# xilinx_platform_cable_iii.net
KiCad netlist of a schematic drawn in EAGLE
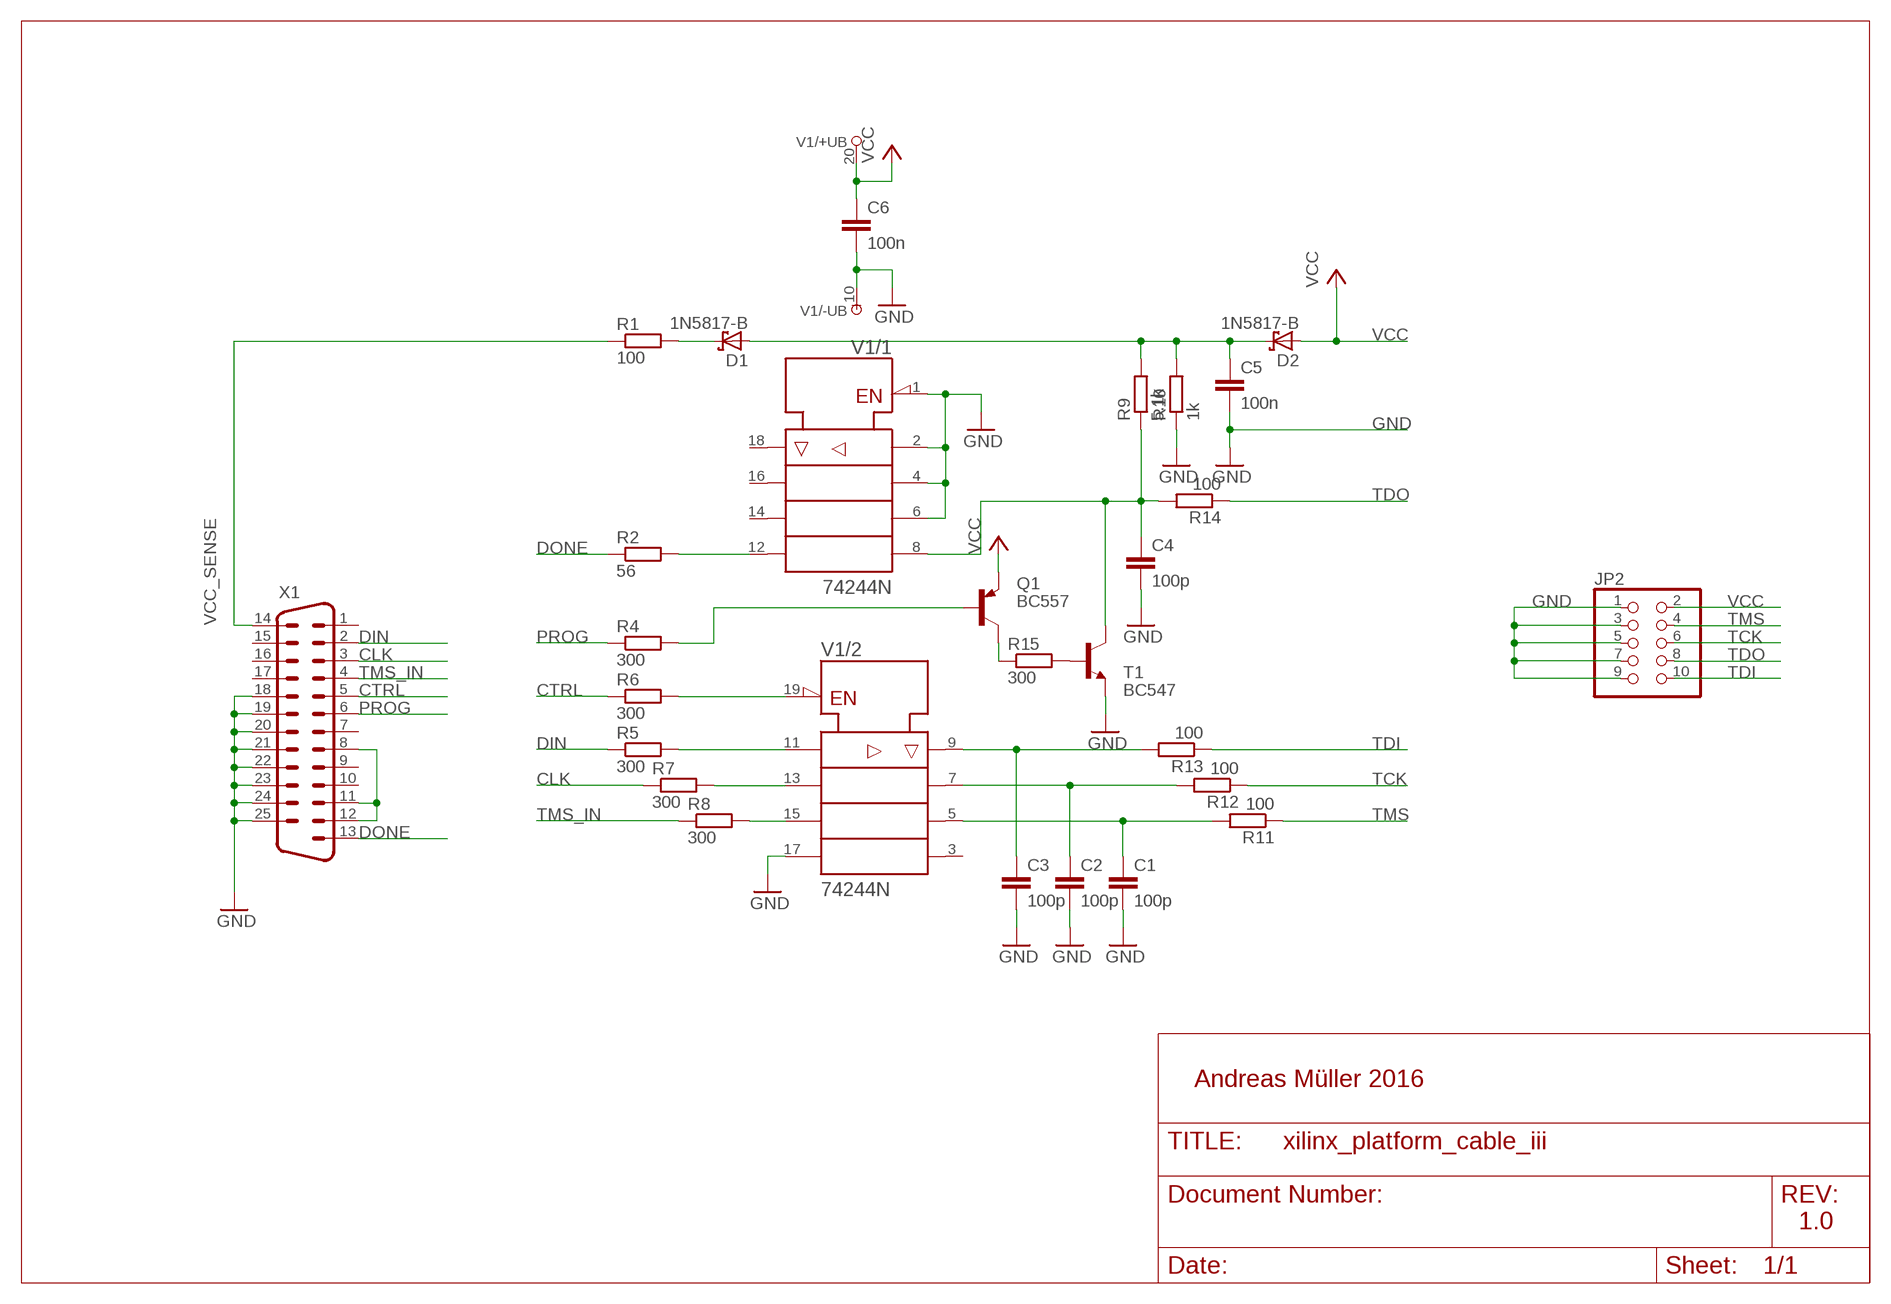
[diagram p0: schematic, sheet 1]

(export (version "E")
  (design (tool "Eeschema 10.0.6"))
  (components
    (comp (ref "C1")
      (value "100p")
      (footprint "eagle-import:C025-030X050")
      (libsource (lib "eagle-import") (part "C-EU025-030X050"))
    )
    (comp (ref "C2")
      (value "100p")
      (footprint "eagle-import:C025-030X050")
      (libsource (lib "eagle-import") (part "C-EU025-030X050"))
    )
    (comp (ref "C3")
      (value "100p")
      (footprint "eagle-import:C025-030X050")
      (libsource (lib "eagle-import") (part "C-EU025-030X050"))
    )
    (comp (ref "C4")
      (value "100p")
      (footprint "eagle-import:C025-030X050")
      (libsource (lib "eagle-import") (part "C-EU025-030X050"))
    )
    (comp (ref "C5")
      (value "100n")
      (footprint "eagle-import:C025-030X050")
      (libsource (lib "eagle-import") (part "C-EU025-030X050"))
    )
    (comp (ref "C6")
      (value "100n")
      (footprint "eagle-import:C025-030X050")
      (libsource (lib "eagle-import") (part "C-EU025-030X050"))
    )
    (comp (ref "D1")
      (value "1N5817-B")
      (footprint "eagle-import:DO41-7.6")
      (libsource (lib "eagle-import") (part "1N5817-B"))
    )
    (comp (ref "D2")
      (value "1N5817-B")
      (footprint "eagle-import:DO41-7.6")
      (libsource (lib "eagle-import") (part "1N5817-B"))
    )
    (comp (ref "JP2")
      (value "PINHD-2X5")
      (footprint "eagle-import:2X05")
      (libsource (lib "eagle-import") (part "PINHD-2X5"))
    )
    (comp (ref "Q1")
      (value "BC557")
      (footprint "eagle-import:TO92")
      (libsource (lib "eagle-import") (part "BC557"))
    )
    (comp (ref "R1")
      (value "100")
      (footprint "eagle-import:0207_12")
      (libsource (lib "eagle-import") (part "R-EU_0207/12"))
    )
    (comp (ref "R2")
      (value "56")
      (footprint "eagle-import:0207_12")
      (libsource (lib "eagle-import") (part "R-EU_0207/12"))
    )
    (comp (ref "R4")
      (value "300")
      (footprint "eagle-import:0207_12")
      (libsource (lib "eagle-import") (part "R-EU_0207/12"))
    )
    (comp (ref "R5")
      (value "300")
      (footprint "eagle-import:0207_12")
      (libsource (lib "eagle-import") (part "R-EU_0207/12"))
    )
    (comp (ref "R6")
      (value "300")
      (footprint "eagle-import:0207_12")
      (libsource (lib "eagle-import") (part "R-EU_0207/12"))
    )
    (comp (ref "R7")
      (value "300")
      (footprint "eagle-import:0207_12")
      (libsource (lib "eagle-import") (part "R-EU_0207/12"))
    )
    (comp (ref "R8")
      (value "300")
      (footprint "eagle-import:0207_12")
      (libsource (lib "eagle-import") (part "R-EU_0207/12"))
    )
    (comp (ref "R9")
      (value "5.1k")
      (footprint "eagle-import:0207_12")
      (libsource (lib "eagle-import") (part "R-EU_0207/12"))
    )
    (comp (ref "R10")
      (value "1k")
      (footprint "eagle-import:0207_12")
      (libsource (lib "eagle-import") (part "R-EU_0207/12"))
    )
    (comp (ref "R11")
      (value "100")
      (footprint "eagle-import:0207_12")
      (libsource (lib "eagle-import") (part "R-EU_0207/12"))
    )
    (comp (ref "R12")
      (value "100")
      (footprint "eagle-import:0207_12")
      (libsource (lib "eagle-import") (part "R-EU_0207/12"))
    )
    (comp (ref "R13")
      (value "100")
      (footprint "eagle-import:0207_12")
      (libsource (lib "eagle-import") (part "R-EU_0207/12"))
    )
    (comp (ref "R14")
      (value "100")
      (footprint "eagle-import:0207_12")
      (libsource (lib "eagle-import") (part "R-EU_0207/12"))
    )
    (comp (ref "R15")
      (value "300")
      (footprint "eagle-import:0207_12")
      (libsource (lib "eagle-import") (part "R-EU_0207/12"))
    )
    (comp (ref "T1")
      (value "BC547")
      (footprint "eagle-import:TO92")
      (libsource (lib "eagle-import") (part "BC547"))
    )
    (comp (ref "V1")
      (value "74244N")
      (footprint "eagle-import:DIL20")
      (libsource (lib "eagle-import") (part "74244N"))
    )
    (comp (ref "X1")
      (value "DB25HP")
      (footprint "eagle-import:M25HP")
      (libsource (lib "eagle-import") (part "DB25HP"))
    )
  )
  (nets
    (net (code "1") (name "/CLK") (class "Default")
      (node (ref "R7") (pin "1") (pinfunction "1_1") (pintype "passive"))
      (node (ref "X1") (pin "3") (pinfunction "3_3") (pintype "passive"))
    )
    (net (code "2") (name "/CTRL") (class "Default")
      (node (ref "R6") (pin "1") (pinfunction "1_1") (pintype "passive"))
      (node (ref "X1") (pin "5") (pinfunction "5_5") (pintype "passive"))
    )
    (net (code "3") (name "/DIN") (class "Default")
      (node (ref "R5") (pin "1") (pinfunction "1_1") (pintype "passive"))
      (node (ref "X1") (pin "2") (pinfunction "2_2") (pintype "passive"))
    )
    (net (code "4") (name "/DONE") (class "Default")
      (node (ref "R2") (pin "1") (pinfunction "1_1") (pintype "passive"))
      (node (ref "X1") (pin "13") (pinfunction "13_13") (pintype "passive"))
    )
    (net (code "5") (name "/PROG") (class "Default")
      (node (ref "R4") (pin "1") (pinfunction "1_1") (pintype "passive"))
      (node (ref "X1") (pin "6") (pinfunction "6_6") (pintype "passive"))
    )
    (net (code "6") (name "/TCK") (class "Default")
      (node (ref "JP2") (pin "6") (pinfunction "6_6") (pintype "passive"))
      (node (ref "R12") (pin "1") (pinfunction "1_1") (pintype "passive"))
    )
    (net (code "7") (name "/TDI") (class "Default")
      (node (ref "JP2") (pin "10") (pinfunction "10_10") (pintype "passive"))
      (node (ref "R13") (pin "1") (pinfunction "1_1") (pintype "passive"))
    )
    (net (code "8") (name "/TDO") (class "Default")
      (node (ref "JP2") (pin "8") (pinfunction "8_8") (pintype "passive"))
      (node (ref "R14") (pin "1") (pinfunction "1_1") (pintype "passive"))
    )
    (net (code "9") (name "/TMS") (class "Default")
      (node (ref "JP2") (pin "4") (pinfunction "4_4") (pintype "passive"))
      (node (ref "R11") (pin "1") (pinfunction "1_1") (pintype "passive"))
    )
    (net (code "10") (name "/TMS_IN") (class "Default")
      (node (ref "R8") (pin "1") (pinfunction "1_1") (pintype "passive"))
      (node (ref "X1") (pin "4") (pinfunction "4_4") (pintype "passive"))
    )
    (net (code "11") (name "/VCC_SENSE") (class "Default")
      (node (ref "R1") (pin "1") (pinfunction "1_1") (pintype "passive"))
      (node (ref "X1") (pin "14") (pinfunction "14_14") (pintype "passive"))
    )
    (net (code "12") (name "GND") (class "Default")
      (node (ref "C1") (pin "2") (pinfunction "2_2") (pintype "passive"))
      (node (ref "C2") (pin "2") (pinfunction "2_2") (pintype "passive"))
      (node (ref "C3") (pin "2") (pinfunction "2_2") (pintype "passive"))
      (node (ref "C4") (pin "2") (pinfunction "2_2") (pintype "passive"))
      (node (ref "C5") (pin "2") (pinfunction "2_2") (pintype "passive"))
      (node (ref "C6") (pin "2") (pinfunction "2_2") (pintype "passive"))
      (node (ref "JP2") (pin "1") (pinfunction "1_1") (pintype "passive"))
      (node (ref "JP2") (pin "3") (pinfunction "3_3") (pintype "passive"))
      (node (ref "JP2") (pin "5") (pinfunction "5_5") (pintype "passive"))
      (node (ref "JP2") (pin "7") (pinfunction "7_7") (pintype "passive"))
      (node (ref "JP2") (pin "9") (pinfunction "9_9") (pintype "passive"))
      (node (ref "R10") (pin "1") (pinfunction "1_1") (pintype "passive"))
      (node (ref "T1") (pin "1") (pinfunction "E_1") (pintype "passive"))
      (node (ref "V1") (pin "1") (pinfunction "~{G}_1") (pintype "input"))
      (node (ref "V1") (pin "10") (pinfunction "-UB_10") (pintype "power_in"))
      (node (ref "V1") (pin "17") (pinfunction "A4_17") (pintype "input"))
      (node (ref "V1") (pin "2") (pinfunction "A1_2") (pintype "input"))
      (node (ref "V1") (pin "4") (pinfunction "A2_4") (pintype "input"))
      (node (ref "V1") (pin "6") (pinfunction "A3_6") (pintype "input"))
      (node (ref "X1") (pin "18") (pinfunction "18_18") (pintype "passive"))
      (node (ref "X1") (pin "19") (pinfunction "19_19") (pintype "passive"))
      (node (ref "X1") (pin "20") (pinfunction "20_20") (pintype "passive"))
      (node (ref "X1") (pin "21") (pinfunction "21_21") (pintype "passive"))
      (node (ref "X1") (pin "22") (pinfunction "22_22") (pintype "passive"))
      (node (ref "X1") (pin "23") (pinfunction "23_23") (pintype "passive"))
      (node (ref "X1") (pin "24") (pinfunction "24_24") (pintype "passive"))
      (node (ref "X1") (pin "25") (pinfunction "25_25") (pintype "passive"))
    )
    (net (code "13") (name "Net-(C5-Pad1)") (class "Default")
      (node (ref "C5") (pin "1") (pinfunction "1_1") (pintype "passive"))
      (node (ref "D1") (pin "A") (pinfunction "A_A") (pintype "passive"))
      (node (ref "D2") (pin "C") (pinfunction "C_C") (pintype "passive"))
      (node (ref "R10") (pin "2") (pinfunction "2_2") (pintype "passive"))
      (node (ref "R9") (pin "2") (pinfunction "2_2") (pintype "passive"))
    )
    (net (code "14") (name "Net-(D1-PadC)") (class "Default")
      (node (ref "D1") (pin "C") (pinfunction "C_C") (pintype "passive"))
      (node (ref "R1") (pin "2") (pinfunction "2_2") (pintype "passive"))
    )
    (net (code "15") (name "Net-(Q1-B)") (class "Default")
      (node (ref "Q1") (pin "2") (pinfunction "B_2") (pintype "passive"))
      (node (ref "R4") (pin "2") (pinfunction "2_2") (pintype "passive"))
    )
    (net (code "16") (name "Net-(Q1-C)") (class "Default")
      (node (ref "Q1") (pin "3") (pinfunction "C_3") (pintype "passive"))
      (node (ref "R15") (pin "1") (pinfunction "1_1") (pintype "passive"))
    )
    (net (code "17") (name "Net-(T1-B)") (class "Default")
      (node (ref "R15") (pin "2") (pinfunction "2_2") (pintype "passive"))
      (node (ref "T1") (pin "2") (pinfunction "B_2") (pintype "passive"))
    )
    (net (code "18") (name "Net-(T1-C)") (class "Default")
      (node (ref "C4") (pin "1") (pinfunction "1_1") (pintype "passive"))
      (node (ref "R14") (pin "2") (pinfunction "2_2") (pintype "passive"))
      (node (ref "R9") (pin "1") (pinfunction "1_1") (pintype "passive"))
      (node (ref "T1") (pin "3") (pinfunction "C_3") (pintype "passive"))
      (node (ref "V1") (pin "8") (pinfunction "A4_8") (pintype "input"))
    )
    (net (code "19") (name "Net-(V1C-Y4)") (class "Default")
      (node (ref "R2") (pin "2") (pinfunction "2_2") (pintype "passive"))
      (node (ref "V1") (pin "12") (pinfunction "Y4_12") (pintype "tri_state"))
    )
    (net (code "20") (name "Net-(V1D-A1)") (class "Default")
      (node (ref "R5") (pin "2") (pinfunction "2_2") (pintype "passive"))
      (node (ref "V1") (pin "11") (pinfunction "A1_11") (pintype "input"))
    )
    (net (code "21") (name "Net-(V1D-A2)") (class "Default")
      (node (ref "R7") (pin "2") (pinfunction "2_2") (pintype "passive"))
      (node (ref "V1") (pin "13") (pinfunction "A2_13") (pintype "input"))
    )
    (net (code "22") (name "Net-(V1D-A3)") (class "Default")
      (node (ref "R8") (pin "2") (pinfunction "2_2") (pintype "passive"))
      (node (ref "V1") (pin "15") (pinfunction "A3_15") (pintype "input"))
    )
    (net (code "23") (name "Net-(V1D-Y1)") (class "Default")
      (node (ref "C3") (pin "1") (pinfunction "1_1") (pintype "passive"))
      (node (ref "R13") (pin "2") (pinfunction "2_2") (pintype "passive"))
      (node (ref "V1") (pin "9") (pinfunction "Y1_9") (pintype "tri_state"))
    )
    (net (code "24") (name "Net-(V1D-Y2)") (class "Default")
      (node (ref "C2") (pin "1") (pinfunction "1_1") (pintype "passive"))
      (node (ref "R12") (pin "2") (pinfunction "2_2") (pintype "passive"))
      (node (ref "V1") (pin "7") (pinfunction "Y2_7") (pintype "tri_state"))
    )
    (net (code "25") (name "Net-(V1D-Y3)") (class "Default")
      (node (ref "C1") (pin "1") (pinfunction "1_1") (pintype "passive"))
      (node (ref "R11") (pin "2") (pinfunction "2_2") (pintype "passive"))
      (node (ref "V1") (pin "5") (pinfunction "Y3_5") (pintype "tri_state"))
    )
    (net (code "26") (name "Net-(V1D-~{G})") (class "Default")
      (node (ref "R6") (pin "2") (pinfunction "2_2") (pintype "passive"))
      (node (ref "V1") (pin "19") (pinfunction "~{G}_19") (pintype "input"))
    )
    (net (code "27") (name "Net-(X1-Pad11)") (class "Default")
      (node (ref "X1") (pin "11") (pinfunction "11_11") (pintype "passive"))
      (node (ref "X1") (pin "12") (pinfunction "12_12") (pintype "passive"))
      (node (ref "X1") (pin "8") (pinfunction "8_8") (pintype "passive"))
    )
    (net (code "28") (name "VCC") (class "Default")
      (node (ref "C6") (pin "1") (pinfunction "1_1") (pintype "passive"))
      (node (ref "D2") (pin "A") (pinfunction "A_A") (pintype "passive"))
      (node (ref "JP2") (pin "2") (pinfunction "2_2") (pintype "passive"))
      (node (ref "Q1") (pin "1") (pinfunction "E_1") (pintype "passive"))
      (node (ref "V1") (pin "20") (pinfunction "+UB_20") (pintype "power_in"))
    )
    (net (code "29") (name "unconnected-(V1C-Y1-Pad18)") (class "Default")
      (node (ref "V1") (pin "18") (pinfunction "Y1_18") (pintype "tri_state"))
    )
    (net (code "30") (name "unconnected-(V1C-Y2-Pad16)") (class "Default")
      (node (ref "V1") (pin "16") (pinfunction "Y2_16") (pintype "tri_state"))
    )
    (net (code "31") (name "unconnected-(V1C-Y3-Pad14)") (class "Default")
      (node (ref "V1") (pin "14") (pinfunction "Y3_14") (pintype "tri_state"))
    )
    (net (code "32") (name "unconnected-(V1D-Y4-Pad3)") (class "Default")
      (node (ref "V1") (pin "3") (pinfunction "Y4_3") (pintype "tri_state"))
    )
    (net (code "33") (name "unconnected-(X1-Pad1)") (class "Default")
      (node (ref "X1") (pin "1") (pinfunction "1_1") (pintype "passive"))
    )
    (net (code "34") (name "unconnected-(X1-Pad7)") (class "Default")
      (node (ref "X1") (pin "7") (pinfunction "7_7") (pintype "passive"))
    )
    (net (code "35") (name "unconnected-(X1-Pad9)") (class "Default")
      (node (ref "X1") (pin "9") (pinfunction "9_9") (pintype "passive"))
    )
    (net (code "36") (name "unconnected-(X1-Pad10)") (class "Default")
      (node (ref "X1") (pin "10") (pinfunction "10_10") (pintype "passive"))
    )
    (net (code "37") (name "unconnected-(X1-Pad15)") (class "Default")
      (node (ref "X1") (pin "15") (pinfunction "15_15") (pintype "passive"))
    )
    (net (code "38") (name "unconnected-(X1-Pad16)") (class "Default")
      (node (ref "X1") (pin "16") (pinfunction "16_16") (pintype "passive"))
    )
    (net (code "39") (name "unconnected-(X1-Pad17)") (class "Default")
      (node (ref "X1") (pin "17") (pinfunction "17_17") (pintype "passive"))
    )
  )
)
